# IV51.net
KiCad netlist of a schematic drawn in EAGLE
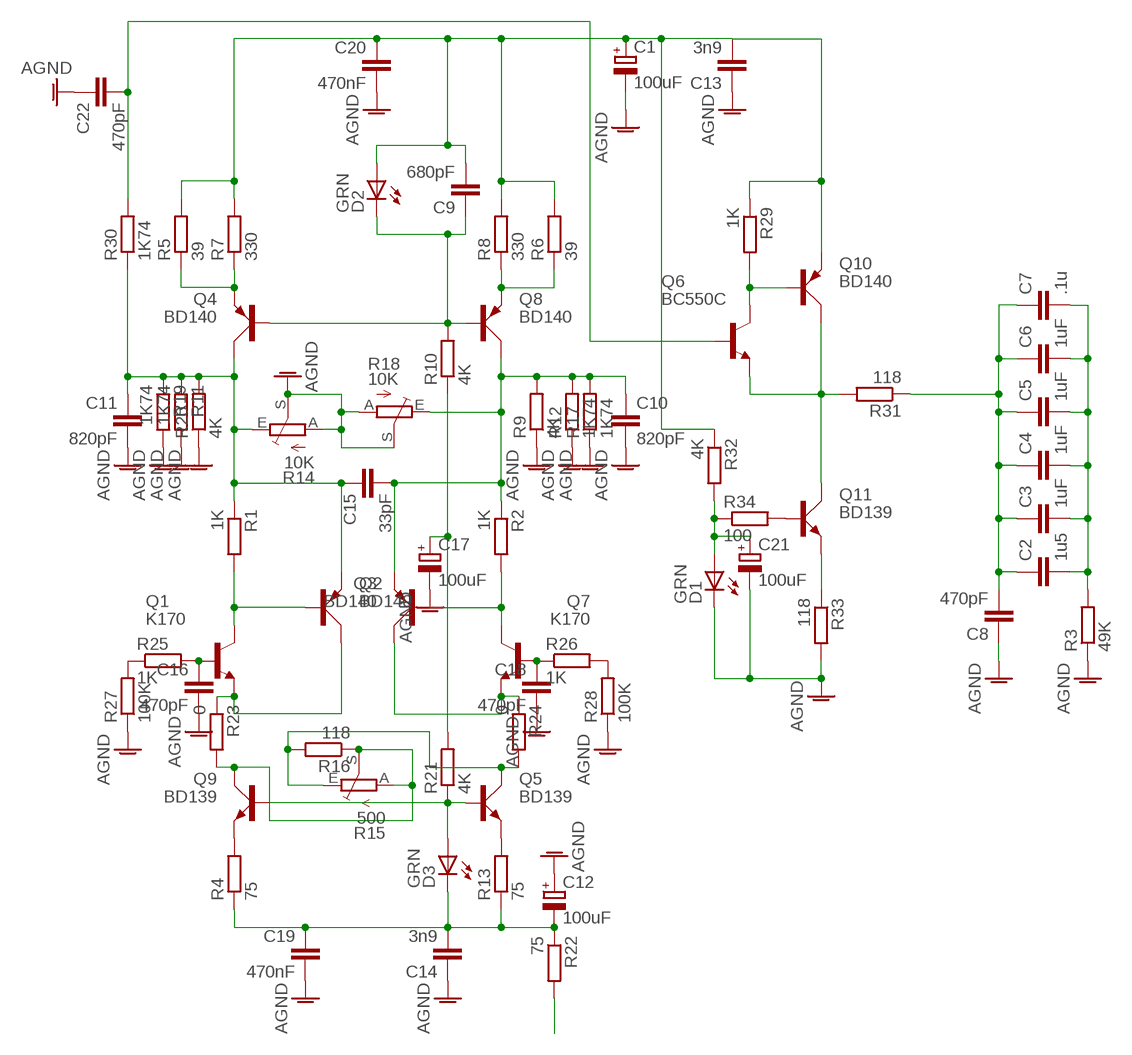
[diagram p0: schematic, sheet 1]

(export (version "E")
  (design (tool "Eeschema 10.0.6"))
  (components
    (comp (ref "C1")
      (value "100uF")
      (footprint "eagle-import:E5-10,5")
      (libsource (lib "eagle-import") (part "CPOL-EUE5-10.5"))
    )
    (comp (ref "C2")
      (value "1u5")
      (footprint "eagle-import:C275-134X316")
      (libsource (lib "eagle-import") (part "C-EU275-134X316"))
    )
    (comp (ref "C3")
      (value "1uF")
      (footprint "eagle-import:C275-134X316")
      (libsource (lib "eagle-import") (part "C-EU275-134X316"))
    )
    (comp (ref "C4")
      (value "1uF")
      (footprint "eagle-import:C275-134X316")
      (libsource (lib "eagle-import") (part "C-EU275-134X316"))
    )
    (comp (ref "C5")
      (value "1uF")
      (footprint "eagle-import:C275-134X316")
      (libsource (lib "eagle-import") (part "C-EU275-134X316"))
    )
    (comp (ref "C6")
      (value "1uF")
      (footprint "eagle-import:C275-134X316")
      (libsource (lib "eagle-import") (part "C-EU275-134X316"))
    )
    (comp (ref "C7")
      (value ".1u")
      (footprint "eagle-import:C050-075X075")
      (libsource (lib "eagle-import") (part "C-EU050-075X075"))
    )
    (comp (ref "C8")
      (value "470pF")
      (footprint "eagle-import:C102-043X133")
      (libsource (lib "eagle-import") (part "C-EU102-043X133"))
    )
    (comp (ref "C9")
      (value "680pF")
      (footprint "eagle-import:C050-045X075")
      (libsource (lib "eagle-import") (part "C-EU050-045X075"))
    )
    (comp (ref "C10")
      (value "820pF")
      (footprint "eagle-import:C075-032X103")
      (libsource (lib "eagle-import") (part "C-EU075-032X103"))
    )
    (comp (ref "C11")
      (value "820pF")
      (footprint "eagle-import:C075-032X103")
      (libsource (lib "eagle-import") (part "C-EU075-032X103"))
    )
    (comp (ref "C12")
      (value "100uF")
      (footprint "eagle-import:E5-10,5")
      (libsource (lib "eagle-import") (part "CPOL-EUE5-10.5"))
    )
    (comp (ref "C13")
      (value "3n9")
      (footprint "eagle-import:C1210")
      (libsource (lib "eagle-import") (part "C-EUC1210"))
    )
    (comp (ref "C14")
      (value "3n9")
      (footprint "eagle-import:C1210")
      (libsource (lib "eagle-import") (part "C-EUC1210"))
    )
    (comp (ref "C15")
      (value "33pF")
      (footprint "eagle-import:C1210")
      (libsource (lib "eagle-import") (part "C-EUC1210"))
    )
    (comp (ref "C16")
      (value "470pF")
      (footprint "eagle-import:C102-043X133")
      (libsource (lib "eagle-import") (part "C-EU102-043X133"))
    )
    (comp (ref "C17")
      (value "100uF")
      (footprint "eagle-import:E3,5-8")
      (libsource (lib "eagle-import") (part "CPOL-EUE3.5-8"))
    )
    (comp (ref "C18")
      (value "470pF")
      (footprint "eagle-import:C102-043X133")
      (libsource (lib "eagle-import") (part "C-EU102-043X133"))
    )
    (comp (ref "C19")
      (value "470nF")
      (footprint "eagle-import:C102-043X133")
      (libsource (lib "eagle-import") (part "C-EU102-043X133"))
    )
    (comp (ref "C20")
      (value "470nF")
      (footprint "eagle-import:C102-043X133")
      (libsource (lib "eagle-import") (part "C-EU102-043X133"))
    )
    (comp (ref "C21")
      (value "100uF")
      (footprint "eagle-import:E3,5-8")
      (libsource (lib "eagle-import") (part "CPOL-EUE3.5-8"))
    )
    (comp (ref "C22")
      (value "470pF")
      (footprint "eagle-import:C075-042X103")
      (libsource (lib "eagle-import") (part "C-EU075-042X103"))
    )
    (comp (ref "D1")
      (value "GRN")
      (footprint "eagle-import:SFH482")
      (libsource (lib "eagle-import") (part "SFH482"))
    )
    (comp (ref "D2")
      (value "GRN")
      (footprint "eagle-import:SFH482")
      (libsource (lib "eagle-import") (part "SFH482"))
    )
    (comp (ref "D3")
      (value "GRN")
      (footprint "eagle-import:SFH482")
      (libsource (lib "eagle-import") (part "SFH482"))
    )
    (comp (ref "Q1")
      (value "K170")
      (footprint "eagle-import:TO92-EBC")
      (libsource (lib "eagle-import") (part "BC549B"))
    )
    (comp (ref "Q2")
      (value "BD140")
      (footprint "eagle-import:TO126AV")
      (libsource (lib "eagle-import") (part "BD140"))
    )
    (comp (ref "Q3")
      (value "BD140")
      (footprint "eagle-import:TO126AV")
      (libsource (lib "eagle-import") (part "BD140"))
    )
    (comp (ref "Q4")
      (value "BD140")
      (footprint "eagle-import:TO126AV")
      (libsource (lib "eagle-import") (part "BD140"))
    )
    (comp (ref "Q5")
      (value "BD139")
      (footprint "eagle-import:TO126AV")
      (libsource (lib "eagle-import") (part "BD139"))
    )
    (comp (ref "Q6")
      (value "BC550C")
      (footprint "eagle-import:TO92-EBC")
      (libsource (lib "eagle-import") (part "BC549B"))
    )
    (comp (ref "Q7")
      (value "K170")
      (footprint "eagle-import:TO92-EBC")
      (libsource (lib "eagle-import") (part "BC549B"))
    )
    (comp (ref "Q8")
      (value "BD140")
      (footprint "eagle-import:TO126AV")
      (libsource (lib "eagle-import") (part "BD140"))
    )
    (comp (ref "Q9")
      (value "BD139")
      (footprint "eagle-import:TO126AV")
      (libsource (lib "eagle-import") (part "BD139"))
    )
    (comp (ref "Q10")
      (value "BD140")
      (footprint "eagle-import:TO126AV")
      (libsource (lib "eagle-import") (part "BD140"))
    )
    (comp (ref "Q11")
      (value "BD139")
      (footprint "eagle-import:TO126AV")
      (libsource (lib "eagle-import") (part "BD139"))
    )
    (comp (ref "R1")
      (value "1K")
      (footprint "eagle-import:0309_12")
      (libsource (lib "eagle-import") (part "R-EU_0309/12"))
    )
    (comp (ref "R2")
      (value "1K")
      (footprint "eagle-import:0309_12")
      (libsource (lib "eagle-import") (part "R-EU_0309/12"))
    )
    (comp (ref "R3")
      (value "49K")
      (footprint "eagle-import:0309_12")
      (libsource (lib "eagle-import") (part "R-EU_0309/12"))
    )
    (comp (ref "R4")
      (value "75")
      (footprint "eagle-import:0309_12")
      (libsource (lib "eagle-import") (part "R-EU_0309/12"))
    )
    (comp (ref "R5")
      (value "39")
      (footprint "eagle-import:0309_12")
      (libsource (lib "eagle-import") (part "R-EU_0309/12"))
    )
    (comp (ref "R6")
      (value "39")
      (footprint "eagle-import:0309_12")
      (libsource (lib "eagle-import") (part "R-EU_0309/12"))
    )
    (comp (ref "R7")
      (value "330")
      (footprint "eagle-import:0309_12")
      (libsource (lib "eagle-import") (part "R-EU_0309/12"))
    )
    (comp (ref "R8")
      (value "330")
      (footprint "eagle-import:0309_12")
      (libsource (lib "eagle-import") (part "R-EU_0309/12"))
    )
    (comp (ref "R9")
      (value "4K")
      (footprint "eagle-import:0309_12")
      (libsource (lib "eagle-import") (part "R-EU_0309/12"))
    )
    (comp (ref "R10")
      (value "4K")
      (footprint "eagle-import:0309_12")
      (libsource (lib "eagle-import") (part "R-EU_0309/12"))
    )
    (comp (ref "R11")
      (value "1K74")
      (footprint "eagle-import:0309_12")
      (libsource (lib "eagle-import") (part "R-EU_0309/12"))
    )
    (comp (ref "R12")
      (value "1K74")
      (footprint "eagle-import:0309_12")
      (libsource (lib "eagle-import") (part "R-EU_0309/12"))
    )
    (comp (ref "R13")
      (value "75")
      (footprint "eagle-import:0309_12")
      (libsource (lib "eagle-import") (part "R-EU_0309/12"))
    )
    (comp (ref "R14")
      (value "10K")
      (footprint "eagle-import:RJ9W")
      (libsource (lib "eagle-import") (part "TRIM_EU-RJ9W"))
    )
    (comp (ref "R15")
      (value "500")
      (footprint "eagle-import:PT-SPIN")
      (libsource (lib "eagle-import") (part "TRIM_EU-PTSPIN"))
    )
    (comp (ref "R16")
      (value "118")
      (footprint "eagle-import:0309_12")
      (libsource (lib "eagle-import") (part "R-EU_0309/12"))
    )
    (comp (ref "R17")
      (value "1K74")
      (footprint "eagle-import:0309_12")
      (libsource (lib "eagle-import") (part "R-EU_0309/12"))
    )
    (comp (ref "R18")
      (value "10K")
      (footprint "eagle-import:RJ9W")
      (libsource (lib "eagle-import") (part "TRIM_EU-RJ9W"))
    )
    (comp (ref "R19")
      (value "1K74")
      (footprint "eagle-import:0309_12")
      (libsource (lib "eagle-import") (part "R-EU_0309/12"))
    )
    (comp (ref "R20")
      (value "4K")
      (footprint "eagle-import:0309_12")
      (libsource (lib "eagle-import") (part "R-EU_0309/12"))
    )
    (comp (ref "R21")
      (value "4K")
      (footprint "eagle-import:0309_12")
      (libsource (lib "eagle-import") (part "R-EU_0309/12"))
    )
    (comp (ref "R22")
      (value "75")
      (footprint "eagle-import:0309_12")
      (libsource (lib "eagle-import") (part "R-EU_0309/12"))
    )
    (comp (ref "R23")
      (value "0")
      (footprint "eagle-import:0309_10")
      (libsource (lib "eagle-import") (part "R-EU_0309/10"))
    )
    (comp (ref "R24")
      (value "0")
      (footprint "eagle-import:0309_10")
      (libsource (lib "eagle-import") (part "R-EU_0309/10"))
    )
    (comp (ref "R25")
      (value "1K")
      (footprint "eagle-import:0309_12")
      (libsource (lib "eagle-import") (part "R-EU_0309/12"))
    )
    (comp (ref "R26")
      (value "1K")
      (footprint "eagle-import:0309_12")
      (libsource (lib "eagle-import") (part "R-EU_0309/12"))
    )
    (comp (ref "R27")
      (value "100K")
      (footprint "eagle-import:0309_12")
      (libsource (lib "eagle-import") (part "R-EU_0309/12"))
    )
    (comp (ref "R28")
      (value "100K")
      (footprint "eagle-import:0309_12")
      (libsource (lib "eagle-import") (part "R-EU_0309/12"))
    )
    (comp (ref "R29")
      (value "1K")
      (footprint "eagle-import:R1210")
      (libsource (lib "eagle-import") (part "R-EU_R1210"))
    )
    (comp (ref "R30")
      (value "1K74")
      (footprint "eagle-import:0309_12")
      (libsource (lib "eagle-import") (part "R-EU_0309/12"))
    )
    (comp (ref "R31")
      (value "118")
      (footprint "eagle-import:0309_12")
      (libsource (lib "eagle-import") (part "R-EU_0309/12"))
    )
    (comp (ref "R32")
      (value "4K")
      (footprint "eagle-import:0309_12")
      (libsource (lib "eagle-import") (part "R-EU_0309/12"))
    )
    (comp (ref "R33")
      (value "118")
      (footprint "eagle-import:0309_12")
      (libsource (lib "eagle-import") (part "R-EU_0309/12"))
    )
    (comp (ref "R34")
      (value "100")
      (footprint "eagle-import:R1210")
      (libsource (lib "eagle-import") (part "R-EU_R1210"))
    )
  )
  (nets
    (net (code "1") (name "AGND") (class "Default")
      (node (ref "C1") (pin "-") (pinfunction "-_-") (pintype "passive"))
      (node (ref "C10") (pin "2") (pinfunction "2_2") (pintype "passive"))
      (node (ref "C11") (pin "2") (pinfunction "2_2") (pintype "passive"))
      (node (ref "C12") (pin "+") (pinfunction "+_+") (pintype "passive"))
      (node (ref "C13") (pin "1") (pinfunction "1_1") (pintype "passive"))
      (node (ref "C14") (pin "1") (pinfunction "1_1") (pintype "passive"))
      (node (ref "C16") (pin "2") (pinfunction "2_2") (pintype "passive"))
      (node (ref "C17") (pin "-") (pinfunction "-_-") (pintype "passive"))
      (node (ref "C18") (pin "2") (pinfunction "2_2") (pintype "passive"))
      (node (ref "C19") (pin "2") (pinfunction "2_2") (pintype "passive"))
      (node (ref "C20") (pin "2") (pinfunction "2_2") (pintype "passive"))
      (node (ref "C21") (pin "-") (pinfunction "-_-") (pintype "passive"))
      (node (ref "C22") (pin "1") (pinfunction "1_1") (pintype "passive"))
      (node (ref "C8") (pin "1") (pinfunction "1_1") (pintype "passive"))
      (node (ref "D1") (pin "K") (pinfunction "C_K") (pintype "passive"))
      (node (ref "R11") (pin "2") (pinfunction "2_2") (pintype "passive"))
      (node (ref "R12") (pin "1") (pinfunction "1_1") (pintype "passive"))
      (node (ref "R14") (pin "A") (pinfunction "A_A") (pintype "passive"))
      (node (ref "R14") (pin "S") (pinfunction "S_S") (pintype "passive"))
      (node (ref "R17") (pin "1") (pinfunction "1_1") (pintype "passive"))
      (node (ref "R18") (pin "A") (pinfunction "A_A") (pintype "passive"))
      (node (ref "R18") (pin "S") (pinfunction "S_S") (pintype "passive"))
      (node (ref "R19") (pin "2") (pinfunction "2_2") (pintype "passive"))
      (node (ref "R20") (pin "1") (pinfunction "1_1") (pintype "passive"))
      (node (ref "R27") (pin "1") (pinfunction "1_1") (pintype "passive"))
      (node (ref "R28") (pin "1") (pinfunction "1_1") (pintype "passive"))
      (node (ref "R3") (pin "1") (pinfunction "1_1") (pintype "passive"))
      (node (ref "R33") (pin "2") (pinfunction "2_2") (pintype "passive"))
      (node (ref "R9") (pin "1") (pinfunction "1_1") (pintype "passive"))
    )
    (net (code "2") (name "Net-(C1-Pad+)") (class "Default")
      (node (ref "C1") (pin "+") (pinfunction "+_+") (pintype "passive"))
      (node (ref "C13") (pin "2") (pinfunction "2_2") (pintype "passive"))
      (node (ref "C20") (pin "1") (pinfunction "1_1") (pintype "passive"))
      (node (ref "C9") (pin "2") (pinfunction "2_2") (pintype "passive"))
      (node (ref "D2") (pin "A") (pinfunction "A_A") (pintype "passive"))
      (node (ref "Q10") (pin "E") (pinfunction "E_E") (pintype "passive"))
      (node (ref "R29") (pin "1") (pinfunction "1_1") (pintype "passive"))
      (node (ref "R32") (pin "1") (pinfunction "1_1") (pintype "passive"))
      (node (ref "R5") (pin "2") (pinfunction "2_2") (pintype "passive"))
      (node (ref "R6") (pin "2") (pinfunction "2_2") (pintype "passive"))
      (node (ref "R7") (pin "2") (pinfunction "2_2") (pintype "passive"))
      (node (ref "R8") (pin "2") (pinfunction "2_2") (pintype "passive"))
    )
    (net (code "3") (name "Net-(C2-Pad1)") (class "Default")
      (node (ref "C2") (pin "1") (pinfunction "1_1") (pintype "passive"))
      (node (ref "C3") (pin "1") (pinfunction "1_1") (pintype "passive"))
      (node (ref "C4") (pin "1") (pinfunction "1_1") (pintype "passive"))
      (node (ref "C5") (pin "1") (pinfunction "1_1") (pintype "passive"))
      (node (ref "C6") (pin "1") (pinfunction "1_1") (pintype "passive"))
      (node (ref "C7") (pin "1") (pinfunction "1_1") (pintype "passive"))
      (node (ref "C8") (pin "2") (pinfunction "2_2") (pintype "passive"))
      (node (ref "R31") (pin "1") (pinfunction "1_1") (pintype "passive"))
    )
    (net (code "4") (name "Net-(C2-Pad2)") (class "Default")
      (node (ref "C2") (pin "2") (pinfunction "2_2") (pintype "passive"))
      (node (ref "C3") (pin "2") (pinfunction "2_2") (pintype "passive"))
      (node (ref "C4") (pin "2") (pinfunction "2_2") (pintype "passive"))
      (node (ref "C5") (pin "2") (pinfunction "2_2") (pintype "passive"))
      (node (ref "C6") (pin "2") (pinfunction "2_2") (pintype "passive"))
      (node (ref "C7") (pin "2") (pinfunction "2_2") (pintype "passive"))
      (node (ref "R3") (pin "2") (pinfunction "2_2") (pintype "passive"))
    )
    (net (code "5") (name "Net-(C10-Pad1)") (class "Default")
      (node (ref "C10") (pin "1") (pinfunction "1_1") (pintype "passive"))
      (node (ref "C15") (pin "2") (pinfunction "2_2") (pintype "passive"))
      (node (ref "Q3") (pin "E") (pinfunction "E_E") (pintype "passive"))
      (node (ref "Q8") (pin "C") (pinfunction "C_C") (pintype "passive"))
      (node (ref "R12") (pin "2") (pinfunction "2_2") (pintype "passive"))
      (node (ref "R17") (pin "2") (pinfunction "2_2") (pintype "passive"))
      (node (ref "R18") (pin "E") (pinfunction "E_E") (pintype "passive"))
      (node (ref "R2") (pin "1") (pinfunction "1_1") (pintype "passive"))
      (node (ref "R9") (pin "2") (pinfunction "2_2") (pintype "passive"))
    )
    (net (code "6") (name "Net-(C11-Pad1)") (class "Default")
      (node (ref "C11") (pin "1") (pinfunction "1_1") (pintype "passive"))
      (node (ref "C15") (pin "1") (pinfunction "1_1") (pintype "passive"))
      (node (ref "Q2") (pin "E") (pinfunction "E_E") (pintype "passive"))
      (node (ref "Q4") (pin "C") (pinfunction "C_C") (pintype "passive"))
      (node (ref "R1") (pin "1") (pinfunction "1_1") (pintype "passive"))
      (node (ref "R11") (pin "1") (pinfunction "1_1") (pintype "passive"))
      (node (ref "R14") (pin "E") (pinfunction "E_E") (pintype "passive"))
      (node (ref "R19") (pin "1") (pinfunction "1_1") (pintype "passive"))
      (node (ref "R20") (pin "2") (pinfunction "2_2") (pintype "passive"))
      (node (ref "R30") (pin "1") (pinfunction "1_1") (pintype "passive"))
    )
    (net (code "7") (name "Net-(C16-Pad1)") (class "Default")
      (node (ref "C16") (pin "1") (pinfunction "1_1") (pintype "passive"))
      (node (ref "Q1") (pin "B") (pinfunction "B_B") (pintype "passive"))
      (node (ref "R25") (pin "2") (pinfunction "2_2") (pintype "passive"))
    )
    (net (code "8") (name "Net-(C17-Pad+)") (class "Default")
      (node (ref "C17") (pin "+") (pinfunction "+_+") (pintype "passive"))
      (node (ref "R10") (pin "1") (pinfunction "1_1") (pintype "passive"))
      (node (ref "R21") (pin "2") (pinfunction "2_2") (pintype "passive"))
    )
    (net (code "9") (name "Net-(C18-Pad1)") (class "Default")
      (node (ref "C18") (pin "1") (pinfunction "1_1") (pintype "passive"))
      (node (ref "Q7") (pin "B") (pinfunction "B_B") (pintype "passive"))
      (node (ref "R26") (pin "1") (pinfunction "1_1") (pintype "passive"))
    )
    (net (code "10") (name "Net-(C21-Pad+)") (class "Default")
      (node (ref "C21") (pin "+") (pinfunction "+_+") (pintype "passive"))
      (node (ref "D1") (pin "A") (pinfunction "A_A") (pintype "passive"))
      (node (ref "R32") (pin "2") (pinfunction "2_2") (pintype "passive"))
      (node (ref "R34") (pin "1") (pinfunction "1_1") (pintype "passive"))
    )
    (net (code "11") (name "Net-(C22-Pad2)") (class "Default")
      (node (ref "C22") (pin "2") (pinfunction "2_2") (pintype "passive"))
      (node (ref "Q6") (pin "B") (pinfunction "B_B") (pintype "passive"))
      (node (ref "R30") (pin "2") (pinfunction "2_2") (pintype "passive"))
    )
    (net (code "12") (name "Net-(D2-C)") (class "Default")
      (node (ref "C9") (pin "1") (pinfunction "1_1") (pintype "passive"))
      (node (ref "D2") (pin "K") (pinfunction "C_K") (pintype "passive"))
      (node (ref "Q4") (pin "B") (pinfunction "B_B") (pintype "passive"))
      (node (ref "Q8") (pin "B") (pinfunction "B_B") (pintype "passive"))
      (node (ref "R10") (pin "2") (pinfunction "2_2") (pintype "passive"))
    )
    (net (code "13") (name "Net-(D3-C)") (class "Default")
      (node (ref "C12") (pin "-") (pinfunction "-_-") (pintype "passive"))
      (node (ref "C14") (pin "2") (pinfunction "2_2") (pintype "passive"))
      (node (ref "C19") (pin "1") (pinfunction "1_1") (pintype "passive"))
      (node (ref "D3") (pin "K") (pinfunction "C_K") (pintype "passive"))
      (node (ref "R13") (pin "1") (pinfunction "1_1") (pintype "passive"))
      (node (ref "R22") (pin "1") (pinfunction "1_1") (pintype "passive"))
      (node (ref "R4") (pin "1") (pinfunction "1_1") (pintype "passive"))
    )
    (net (code "14") (name "Net-(D3-PadA)") (class "Default")
      (node (ref "D3") (pin "A") (pinfunction "A_A") (pintype "passive"))
      (node (ref "Q5") (pin "B") (pinfunction "B_B") (pintype "passive"))
      (node (ref "Q9") (pin "B") (pinfunction "B_B") (pintype "passive"))
      (node (ref "R21") (pin "1") (pinfunction "1_1") (pintype "passive"))
    )
    (net (code "15") (name "Net-(Q1-PadC)") (class "Default")
      (node (ref "Q1") (pin "C") (pinfunction "C_C") (pintype "passive"))
      (node (ref "Q2") (pin "B") (pinfunction "B_B") (pintype "passive"))
      (node (ref "R1") (pin "2") (pinfunction "2_2") (pintype "passive"))
    )
    (net (code "16") (name "Net-(Q1-PadE)") (class "Default")
      (node (ref "Q1") (pin "E") (pinfunction "E_E") (pintype "passive"))
      (node (ref "Q2") (pin "C") (pinfunction "C_C") (pintype "passive"))
      (node (ref "R23") (pin "1") (pinfunction "1_1") (pintype "passive"))
    )
    (net (code "17") (name "Net-(Q3-PadB)") (class "Default")
      (node (ref "Q3") (pin "B") (pinfunction "B_B") (pintype "passive"))
      (node (ref "Q7") (pin "C") (pinfunction "C_C") (pintype "passive"))
      (node (ref "R2") (pin "2") (pinfunction "2_2") (pintype "passive"))
    )
    (net (code "18") (name "Net-(Q3-PadC)") (class "Default")
      (node (ref "Q3") (pin "C") (pinfunction "C_C") (pintype "passive"))
      (node (ref "Q7") (pin "E") (pinfunction "E_E") (pintype "passive"))
      (node (ref "R24") (pin "1") (pinfunction "1_1") (pintype "passive"))
    )
    (net (code "19") (name "Net-(Q4-PadE)") (class "Default")
      (node (ref "Q4") (pin "E") (pinfunction "E_E") (pintype "passive"))
      (node (ref "R5") (pin "1") (pinfunction "1_1") (pintype "passive"))
      (node (ref "R7") (pin "1") (pinfunction "1_1") (pintype "passive"))
    )
    (net (code "20") (name "Net-(Q5-PadC)") (class "Default")
      (node (ref "Q5") (pin "C") (pinfunction "C_C") (pintype "passive"))
      (node (ref "R15") (pin "E") (pinfunction "E_E") (pintype "passive"))
      (node (ref "R16") (pin "2") (pinfunction "2_2") (pintype "passive"))
      (node (ref "R24") (pin "2") (pinfunction "2_2") (pintype "passive"))
    )
    (net (code "21") (name "Net-(Q5-PadE)") (class "Default")
      (node (ref "Q5") (pin "E") (pinfunction "E_E") (pintype "passive"))
      (node (ref "R13") (pin "2") (pinfunction "2_2") (pintype "passive"))
    )
    (net (code "22") (name "Net-(Q8-PadE)") (class "Default")
      (node (ref "Q8") (pin "E") (pinfunction "E_E") (pintype "passive"))
      (node (ref "R6") (pin "1") (pinfunction "1_1") (pintype "passive"))
      (node (ref "R8") (pin "1") (pinfunction "1_1") (pintype "passive"))
    )
    (net (code "23") (name "Net-(Q9-PadC)") (class "Default")
      (node (ref "Q9") (pin "C") (pinfunction "C_C") (pintype "passive"))
      (node (ref "R15") (pin "A") (pinfunction "A_A") (pintype "passive"))
      (node (ref "R15") (pin "S") (pinfunction "S_S") (pintype "passive"))
      (node (ref "R16") (pin "1") (pinfunction "1_1") (pintype "passive"))
      (node (ref "R23") (pin "2") (pinfunction "2_2") (pintype "passive"))
    )
    (net (code "24") (name "Net-(Q9-PadE)") (class "Default")
      (node (ref "Q9") (pin "E") (pinfunction "E_E") (pintype "passive"))
      (node (ref "R4") (pin "2") (pinfunction "2_2") (pintype "passive"))
    )
    (net (code "25") (name "Net-(Q10-PadB)") (class "Default")
      (node (ref "Q10") (pin "B") (pinfunction "B_B") (pintype "passive"))
      (node (ref "Q6") (pin "C") (pinfunction "C_C") (pintype "passive"))
      (node (ref "R29") (pin "2") (pinfunction "2_2") (pintype "passive"))
    )
    (net (code "26") (name "Net-(Q10-PadC)") (class "Default")
      (node (ref "Q10") (pin "C") (pinfunction "C_C") (pintype "passive"))
      (node (ref "Q11") (pin "C") (pinfunction "C_C") (pintype "passive"))
      (node (ref "Q6") (pin "E") (pinfunction "E_E") (pintype "passive"))
      (node (ref "R31") (pin "2") (pinfunction "2_2") (pintype "passive"))
    )
    (net (code "27") (name "Net-(Q11-PadB)") (class "Default")
      (node (ref "Q11") (pin "B") (pinfunction "B_B") (pintype "passive"))
      (node (ref "R34") (pin "2") (pinfunction "2_2") (pintype "passive"))
    )
    (net (code "28") (name "Net-(Q11-PadE)") (class "Default")
      (node (ref "Q11") (pin "E") (pinfunction "E_E") (pintype "passive"))
      (node (ref "R33") (pin "1") (pinfunction "1_1") (pintype "passive"))
    )
    (net (code "29") (name "Net-(R25-Pad1)") (class "Default")
      (node (ref "R25") (pin "1") (pinfunction "1_1") (pintype "passive"))
      (node (ref "R27") (pin "2") (pinfunction "2_2") (pintype "passive"))
    )
    (net (code "30") (name "Net-(R26-Pad2)") (class "Default")
      (node (ref "R26") (pin "2") (pinfunction "2_2") (pintype "passive"))
      (node (ref "R28") (pin "2") (pinfunction "2_2") (pintype "passive"))
    )
    (net (code "31") (name "unconnected-(R22-Pad2)") (class "Default")
      (node (ref "R22") (pin "2") (pinfunction "2_2") (pintype "passive"))
    )
  )
)
